# POE_PD_4_P-Schalter.net
KiCad netlist of a schematic drawn in EAGLE
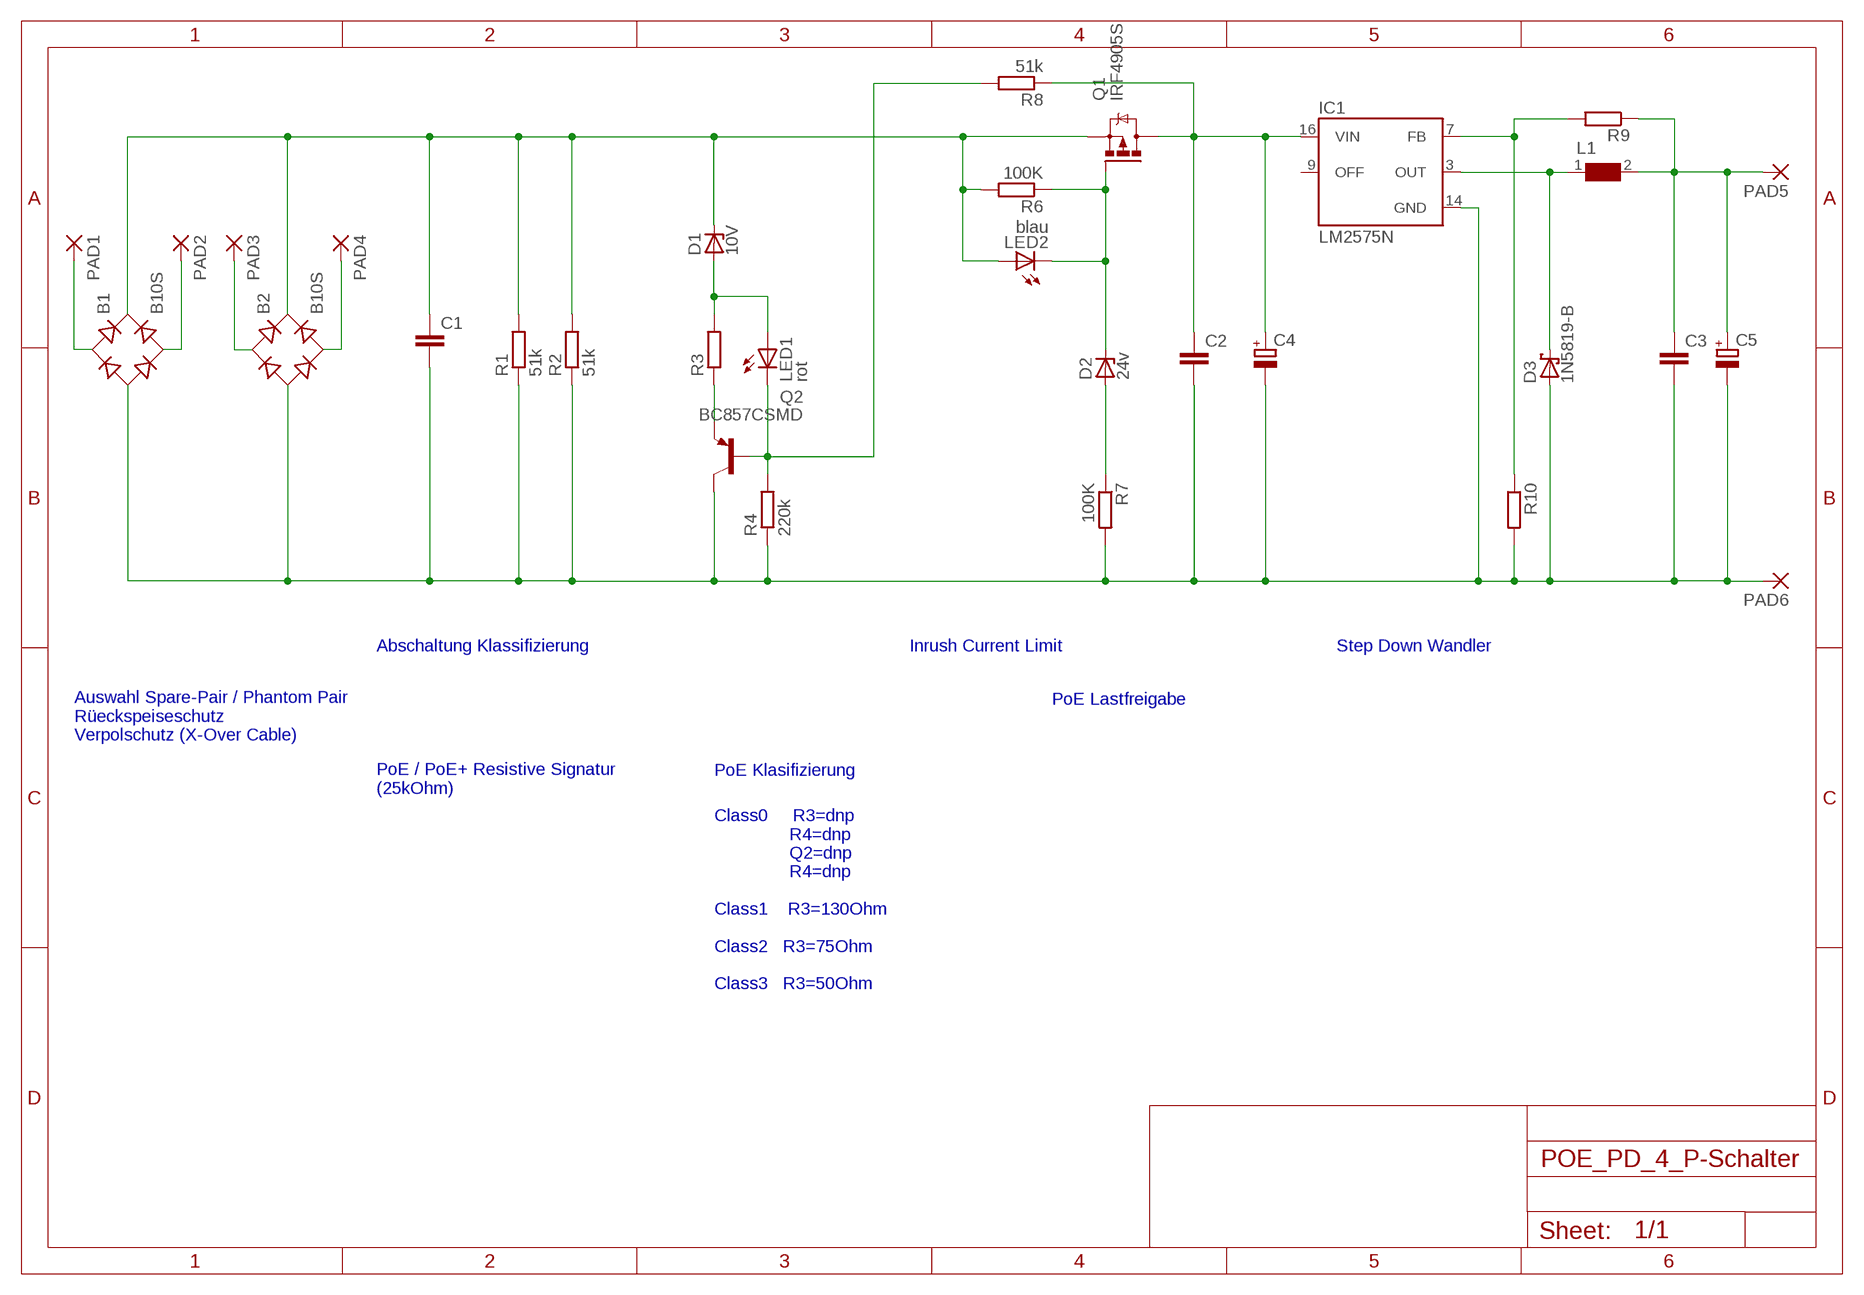
[diagram p0: schematic, sheet 1]

(export (version "E")
  (design (tool "Eeschema 10.0.6"))
  (components
    (comp (ref "B1")
      (value "B10S")
      (footprint "eagle-import:MBS")
      (libsource (lib "eagle-import") (part "BS10"))
    )
    (comp (ref "B2")
      (value "B10S")
      (footprint "eagle-import:MBS")
      (libsource (lib "eagle-import") (part "BS10"))
    )
    (comp (ref "C1")
      (value "C-EUC0805")
      (footprint "eagle-import:C0805")
      (libsource (lib "eagle-import") (part "C-EUC0805"))
    )
    (comp (ref "C2")
      (value "C-EUC0805")
      (footprint "eagle-import:C0805")
      (libsource (lib "eagle-import") (part "C-EUC0805"))
    )
    (comp (ref "C3")
      (value "C-EUC0805")
      (footprint "eagle-import:C0805")
      (libsource (lib "eagle-import") (part "C-EUC0805"))
    )
    (comp (ref "C4")
      (value "CPOL-EU153CLV-0605")
      (footprint "eagle-import:153CLV-0605")
      (libsource (lib "eagle-import") (part "CPOL-EU153CLV-0605"))
    )
    (comp (ref "C5")
      (value "CPOL-EU153CLV-0605")
      (footprint "eagle-import:153CLV-0605")
      (libsource (lib "eagle-import") (part "CPOL-EU153CLV-0605"))
    )
    (comp (ref "D1")
      (value "10V")
      (footprint "eagle-import:SOT23")
      (libsource (lib "eagle-import") (part "ZENER-DIODESOT23"))
    )
    (comp (ref "D2")
      (value "24v")
      (footprint "eagle-import:SOT23")
      (libsource (lib "eagle-import") (part "ZENER-DIODESOT23"))
    )
    (comp (ref "D3")
      (value "1N5819-B")
      (footprint "eagle-import:DO41-7.6")
      (libsource (lib "eagle-import") (part "1N5819-B"))
    )
    (comp (ref "IC1")
      (value "LM2575N")
      (footprint "eagle-import:DIL16")
      (libsource (lib "eagle-import") (part "LM2575N"))
    )
    (comp (ref "L1")
      (value "WE-PD2_S")
      (footprint "eagle-import:WE-PD2_S")
      (libsource (lib "eagle-import") (part "WE-PD2_S"))
    )
    (comp (ref "LED1")
      (value "rot")
      (footprint "eagle-import:CHIP-LED0805")
      (libsource (lib "eagle-import") (part "LEDCHIP-LED0805"))
    )
    (comp (ref "LED2")
      (value "blau")
      (footprint "eagle-import:CHIP-LED0805")
      (libsource (lib "eagle-import") (part "LEDCHIP-LED0805"))
    )
    (comp (ref "PAD1")
      (value "2,15/1,0")
      (footprint "eagle-import:2,15_1,0")
      (libsource (lib "eagle-import") (part "2,15/1,0"))
    )
    (comp (ref "PAD2")
      (value "2,15/1,0")
      (footprint "eagle-import:2,15_1,0")
      (libsource (lib "eagle-import") (part "2,15/1,0"))
    )
    (comp (ref "PAD3")
      (value "2,15/1,0")
      (footprint "eagle-import:2,15_1,0")
      (libsource (lib "eagle-import") (part "2,15/1,0"))
    )
    (comp (ref "PAD4")
      (value "2,15/1,0")
      (footprint "eagle-import:2,15_1,0")
      (libsource (lib "eagle-import") (part "2,15/1,0"))
    )
    (comp (ref "PAD5")
      (value "2,15/1,0")
      (footprint "eagle-import:2,15_1,0")
      (libsource (lib "eagle-import") (part "2,15/1,0"))
    )
    (comp (ref "PAD6")
      (value "2,15/1,0")
      (footprint "eagle-import:2,15_1,0")
      (libsource (lib "eagle-import") (part "2,15/1,0"))
    )
    (comp (ref "Q1")
      (value "IRF4905S")
      (footprint "eagle-import:D-PAK_TO252AA")
      (libsource (lib "eagle-import") (part "IRF?5305R"))
    )
    (comp (ref "Q2")
      (value "BC857CSMD")
      (footprint "eagle-import:SOT23-BEC")
      (libsource (lib "eagle-import") (part "BC857SMDC"))
    )
    (comp (ref "R1")
      (value "51k")
      (footprint "eagle-import:R0603")
      (libsource (lib "eagle-import") (part "R-EU_R0603"))
    )
    (comp (ref "R2")
      (value "51k")
      (footprint "eagle-import:R0603")
      (libsource (lib "eagle-import") (part "R-EU_R0603"))
    )
    (comp (ref "R3")
      (value "R-EU_R0603")
      (footprint "eagle-import:R0603")
      (libsource (lib "eagle-import") (part "R-EU_R0603"))
    )
    (comp (ref "R4")
      (value "220k")
      (footprint "eagle-import:R0603")
      (libsource (lib "eagle-import") (part "R-EU_R0603"))
    )
    (comp (ref "R6")
      (value "100K")
      (footprint "eagle-import:R0603")
      (libsource (lib "eagle-import") (part "R-EU_R0603"))
    )
    (comp (ref "R7")
      (value "100K")
      (footprint "eagle-import:R0603")
      (libsource (lib "eagle-import") (part "R-EU_R0603"))
    )
    (comp (ref "R8")
      (value "51k")
      (footprint "eagle-import:R0603")
      (libsource (lib "eagle-import") (part "R-EU_R0603"))
    )
    (comp (ref "R9")
      (value "R-EU_R0603")
      (footprint "eagle-import:R0603")
      (libsource (lib "eagle-import") (part "R-EU_R0603"))
    )
    (comp (ref "R10")
      (value "R-EU_R0603")
      (footprint "eagle-import:R0603")
      (libsource (lib "eagle-import") (part "R-EU_R0603"))
    )
  )
  (nets
    (net (code "1") (name "Net-(D1-A)") (class "Default")
      (node (ref "D1") (pin "1") (pinfunction "A_1") (pintype "passive"))
      (node (ref "LED1") (pin "A") (pinfunction "A_A") (pintype "passive"))
      (node (ref "R3") (pin "2") (pinfunction "2_2") (pintype "passive"))
    )
    (net (code "2") (name "Net-(D1-C)") (class "Default")
      (node (ref "B1") (pin "+") (pinfunction "+_+") (pintype "passive"))
      (node (ref "B2") (pin "+") (pinfunction "+_+") (pintype "passive"))
      (node (ref "C1") (pin "1") (pinfunction "1_1") (pintype "passive"))
      (node (ref "D1") (pin "3") (pinfunction "C_3") (pintype "passive"))
      (node (ref "LED2") (pin "A") (pinfunction "A_A") (pintype "passive"))
      (node (ref "Q1") (pin "3") (pinfunction "S_3") (pintype "passive"))
      (node (ref "R1") (pin "2") (pinfunction "2_2") (pintype "passive"))
      (node (ref "R2") (pin "2") (pinfunction "2_2") (pintype "passive"))
      (node (ref "R6") (pin "2") (pinfunction "2_2") (pintype "passive"))
    )
    (net (code "3") (name "Net-(D2-A)") (class "Default")
      (node (ref "D2") (pin "1") (pinfunction "A_1") (pintype "passive"))
      (node (ref "R7") (pin "1") (pinfunction "1_1") (pintype "passive"))
    )
    (net (code "4") (name "Net-(D2-C)") (class "Default")
      (node (ref "D2") (pin "3") (pinfunction "C_3") (pintype "passive"))
      (node (ref "LED2") (pin "C") (pinfunction "C_C") (pintype "passive"))
      (node (ref "Q1") (pin "1") (pinfunction "G_1") (pintype "passive"))
      (node (ref "R6") (pin "1") (pinfunction "1_1") (pintype "passive"))
    )
    (net (code "5") (name "Net-(IC1-FB)") (class "Default")
      (node (ref "IC1") (pin "7") (pinfunction "FB_7") (pintype "input"))
      (node (ref "R10") (pin "1") (pinfunction "1_1") (pintype "passive"))
      (node (ref "R9") (pin "2") (pinfunction "2_2") (pintype "passive"))
    )
    (net (code "6") (name "Net-(IC1-GND)") (class "Default")
      (node (ref "B1") (pin "-") (pinfunction "-_-") (pintype "passive"))
      (node (ref "B2") (pin "-") (pinfunction "-_-") (pintype "passive"))
      (node (ref "C1") (pin "2") (pinfunction "2_2") (pintype "passive"))
      (node (ref "C2") (pin "2") (pinfunction "2_2") (pintype "passive"))
      (node (ref "C3") (pin "2") (pinfunction "2_2") (pintype "passive"))
      (node (ref "C4") (pin "-") (pinfunction "-_-") (pintype "passive"))
      (node (ref "C5") (pin "-") (pinfunction "-_-") (pintype "passive"))
      (node (ref "D3") (pin "A") (pinfunction "A_A") (pintype "passive"))
      (node (ref "IC1") (pin "14") (pinfunction "GND_14") (pintype "power_in"))
      (node (ref "PAD6") (pin "1") (pinfunction "P_1") (pintype "passive"))
      (node (ref "Q2") (pin "C") (pinfunction "C_C") (pintype "passive"))
      (node (ref "R1") (pin "1") (pinfunction "1_1") (pintype "passive"))
      (node (ref "R10") (pin "2") (pinfunction "2_2") (pintype "passive"))
      (node (ref "R2") (pin "1") (pinfunction "1_1") (pintype "passive"))
      (node (ref "R4") (pin "1") (pinfunction "1_1") (pintype "passive"))
      (node (ref "R7") (pin "2") (pinfunction "2_2") (pintype "passive"))
    )
    (net (code "7") (name "Net-(IC1-OUT)") (class "Default")
      (node (ref "D3") (pin "C") (pinfunction "C_C") (pintype "passive"))
      (node (ref "IC1") (pin "3") (pinfunction "OUT_3") (pintype "output"))
      (node (ref "L1") (pin "1") (pinfunction "1_1") (pintype "passive"))
    )
    (net (code "8") (name "Net-(IC1-VIN)") (class "Default")
      (node (ref "C2") (pin "1") (pinfunction "1_1") (pintype "passive"))
      (node (ref "C4") (pin "+") (pinfunction "+_+") (pintype "passive"))
      (node (ref "IC1") (pin "16") (pinfunction "VIN_16") (pintype "power_in"))
      (node (ref "Q1") (pin "4") (pinfunction "D_4") (pintype "passive"))
      (node (ref "R8") (pin "1") (pinfunction "1_1") (pintype "passive"))
    )
    (net (code "9") (name "Net-(LED1-PadC)") (class "Default")
      (node (ref "LED1") (pin "C") (pinfunction "C_C") (pintype "passive"))
      (node (ref "Q2") (pin "B") (pinfunction "B_B") (pintype "passive"))
      (node (ref "R4") (pin "2") (pinfunction "2_2") (pintype "passive"))
      (node (ref "R8") (pin "2") (pinfunction "2_2") (pintype "passive"))
    )
    (net (code "10") (name "Net-(PAD1-P)") (class "Default")
      (node (ref "B1") (pin "AC1") (pinfunction "AC1_AC1") (pintype "passive"))
      (node (ref "PAD1") (pin "1") (pinfunction "P_1") (pintype "passive"))
    )
    (net (code "11") (name "Net-(PAD2-P)") (class "Default")
      (node (ref "B1") (pin "AC2") (pinfunction "AC2_AC2") (pintype "passive"))
      (node (ref "PAD2") (pin "1") (pinfunction "P_1") (pintype "passive"))
    )
    (net (code "12") (name "Net-(PAD3-P)") (class "Default")
      (node (ref "B2") (pin "AC1") (pinfunction "AC1_AC1") (pintype "passive"))
      (node (ref "PAD3") (pin "1") (pinfunction "P_1") (pintype "passive"))
    )
    (net (code "13") (name "Net-(PAD4-P)") (class "Default")
      (node (ref "B2") (pin "AC2") (pinfunction "AC2_AC2") (pintype "passive"))
      (node (ref "PAD4") (pin "1") (pinfunction "P_1") (pintype "passive"))
    )
    (net (code "14") (name "Net-(PAD5-P)") (class "Default")
      (node (ref "C3") (pin "1") (pinfunction "1_1") (pintype "passive"))
      (node (ref "C5") (pin "+") (pinfunction "+_+") (pintype "passive"))
      (node (ref "L1") (pin "2") (pinfunction "2_2") (pintype "passive"))
      (node (ref "PAD5") (pin "1") (pinfunction "P_1") (pintype "passive"))
      (node (ref "R9") (pin "1") (pinfunction "1_1") (pintype "passive"))
    )
    (net (code "15") (name "Net-(Q2-PadE)") (class "Default")
      (node (ref "Q2") (pin "E") (pinfunction "E_E") (pintype "passive"))
      (node (ref "R3") (pin "1") (pinfunction "1_1") (pintype "passive"))
    )
    (net (code "16") (name "unconnected-(IC1-OFF-Pad9)") (class "Default")
      (node (ref "IC1") (pin "9") (pinfunction "OFF_9") (pintype "input"))
    )
  )
)
